# TA_v2_Deck.net
KiCad netlist of a schematic drawn in EAGLE
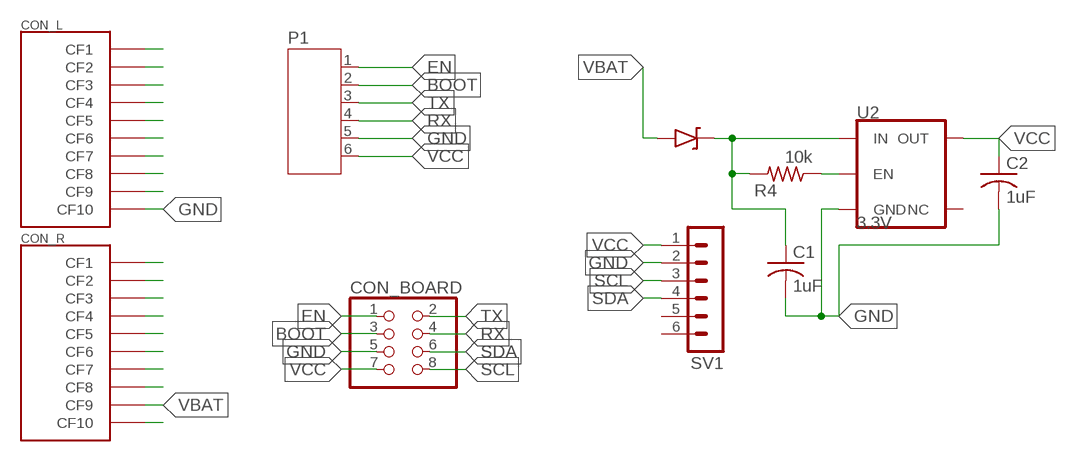
[diagram p0: schematic, sheet 1]

(export (version "E")
  (design (tool "Eeschema 10.0.6"))
  (components
    (comp (ref "C1")
      (value "1uF")
      (footprint "eagle-import:C0805")
      (libsource (lib "eagle-import") (part "C-USC0805"))
    )
    (comp (ref "C2")
      (value "1uF")
      (footprint "eagle-import:C0805")
      (libsource (lib "eagle-import") (part "C-USC0805"))
    )
    (comp (ref "CON_BOARD")
      (value "PINHD-2X4")
      (footprint "eagle-import:2X04")
      (libsource (lib "eagle-import") (part "PINHD-2X4"))
    )
    (comp (ref "CON_L")
      (value "FEMALE_CON")
      (footprint "eagle-import:FEMALE_HEADER_2")
      (libsource (lib "eagle-import") (part "FEMALE_CON"))
    )
    (comp (ref "CON_R")
      (value "FEMALE_CON")
      (footprint "eagle-import:FEMALE_HEADER_2")
      (libsource (lib "eagle-import") (part "FEMALE_CON"))
    )
    (comp (ref "P1")
      (value "JST-PH6")
      (footprint "eagle-import:JST-PH6")
      (libsource (lib "eagle-import") (part "JST-PH6"))
    )
    (comp (ref "R4")
      (value "10k")
      (footprint "eagle-import:R0603")
      (libsource (lib "eagle-import") (part "R-US_R0603"))
    )
    (comp (ref "SV1")
      (value "MA06-1")
      (footprint "eagle-import:MA06-1")
      (libsource (lib "eagle-import") (part "MA06-1"))
    )
    (comp (ref "U$2")
      (value "1N5819")
      (footprint "eagle-import:SOT-323")
      (libsource (lib "eagle-import") (part "1N5819"))
    )
    (comp (ref "U2")
      (value "3.3V")
      (footprint "eagle-import:SOT23-5")
      (libsource (lib "eagle-import") (part "V_REG_AP2112K-3.3V"))
    )
  )
  (nets
    (net (code "1") (name "BOOT") (class "Default")
      (node (ref "CON_BOARD") (pin "3") (pinfunction "3_3") (pintype "passive"))
      (node (ref "P1") (pin "2") (pinfunction "2_2") (pintype "passive"))
    )
    (net (code "2") (name "EN") (class "Default")
      (node (ref "CON_BOARD") (pin "1") (pinfunction "1_1") (pintype "passive"))
      (node (ref "P1") (pin "1") (pinfunction "1_1") (pintype "passive"))
    )
    (net (code "3") (name "GND") (class "Default")
      (node (ref "C1") (pin "2") (pinfunction "2_2") (pintype "passive"))
      (node (ref "C2") (pin "2") (pinfunction "2_2") (pintype "passive"))
      (node (ref "CON_BOARD") (pin "5") (pinfunction "5_5") (pintype "passive"))
      (node (ref "CON_L") (pin "CF10") (pinfunction "CF10_CF10") (pintype "bidirectional"))
      (node (ref "P1") (pin "5") (pinfunction "5_5") (pintype "passive"))
      (node (ref "SV1") (pin "2") (pinfunction "2_2") (pintype "passive"))
      (node (ref "U2") (pin "2") (pinfunction "GND_2") (pintype "input"))
    )
    (net (code "4") (name "Net-(U2-EN)") (class "Default")
      (node (ref "R4") (pin "1") (pinfunction "1_1") (pintype "passive"))
      (node (ref "U2") (pin "3") (pinfunction "EN_3") (pintype "input"))
    )
    (net (code "5") (name "Net-(U2-IN)") (class "Default")
      (node (ref "C1") (pin "1") (pinfunction "1_1") (pintype "passive"))
      (node (ref "R4") (pin "2") (pinfunction "2_2") (pintype "passive"))
      (node (ref "U$2") (pin "K") (pinfunction "K_K") (pintype "bidirectional"))
      (node (ref "U2") (pin "1") (pinfunction "IN_1") (pintype "input"))
    )
    (net (code "6") (name "RX") (class "Default")
      (node (ref "CON_BOARD") (pin "4") (pinfunction "4_4") (pintype "passive"))
      (node (ref "P1") (pin "4") (pinfunction "4_4") (pintype "passive"))
    )
    (net (code "7") (name "SCL") (class "Default")
      (node (ref "CON_BOARD") (pin "8") (pinfunction "8_8") (pintype "passive"))
      (node (ref "SV1") (pin "3") (pinfunction "3_3") (pintype "passive"))
    )
    (net (code "8") (name "SDA") (class "Default")
      (node (ref "CON_BOARD") (pin "6") (pinfunction "6_6") (pintype "passive"))
      (node (ref "SV1") (pin "4") (pinfunction "4_4") (pintype "passive"))
    )
    (net (code "9") (name "TX") (class "Default")
      (node (ref "CON_BOARD") (pin "2") (pinfunction "2_2") (pintype "passive"))
      (node (ref "P1") (pin "3") (pinfunction "3_3") (pintype "passive"))
    )
    (net (code "10") (name "VBAT") (class "Default")
      (node (ref "CON_R") (pin "CF9") (pinfunction "CF9_CF9") (pintype "bidirectional"))
      (node (ref "U$2") (pin "A") (pinfunction "A_A") (pintype "bidirectional"))
    )
    (net (code "11") (name "VCC") (class "Default")
      (node (ref "C2") (pin "1") (pinfunction "1_1") (pintype "passive"))
      (node (ref "CON_BOARD") (pin "7") (pinfunction "7_7") (pintype "passive"))
      (node (ref "P1") (pin "6") (pinfunction "6_6") (pintype "passive"))
      (node (ref "SV1") (pin "1") (pinfunction "1_1") (pintype "passive"))
      (node (ref "U2") (pin "5") (pinfunction "OUT_5") (pintype "passive"))
    )
    (net (code "12") (name "unconnected-(CON_L-PadCF1)") (class "Default")
      (node (ref "CON_L") (pin "CF1") (pinfunction "CF1_CF1") (pintype "bidirectional"))
    )
    (net (code "13") (name "unconnected-(CON_L-PadCF2)") (class "Default")
      (node (ref "CON_L") (pin "CF2") (pinfunction "CF2_CF2") (pintype "bidirectional"))
    )
    (net (code "14") (name "unconnected-(CON_L-PadCF3)") (class "Default")
      (node (ref "CON_L") (pin "CF3") (pinfunction "CF3_CF3") (pintype "bidirectional"))
    )
    (net (code "15") (name "unconnected-(CON_L-PadCF4)") (class "Default")
      (node (ref "CON_L") (pin "CF4") (pinfunction "CF4_CF4") (pintype "bidirectional"))
    )
    (net (code "16") (name "unconnected-(CON_L-PadCF5)") (class "Default")
      (node (ref "CON_L") (pin "CF5") (pinfunction "CF5_CF5") (pintype "bidirectional"))
    )
    (net (code "17") (name "unconnected-(CON_L-PadCF6)") (class "Default")
      (node (ref "CON_L") (pin "CF6") (pinfunction "CF6_CF6") (pintype "bidirectional"))
    )
    (net (code "18") (name "unconnected-(CON_L-PadCF7)") (class "Default")
      (node (ref "CON_L") (pin "CF7") (pinfunction "CF7_CF7") (pintype "bidirectional"))
    )
    (net (code "19") (name "unconnected-(CON_L-PadCF8)") (class "Default")
      (node (ref "CON_L") (pin "CF8") (pinfunction "CF8_CF8") (pintype "bidirectional"))
    )
    (net (code "20") (name "unconnected-(CON_L-PadCF9)") (class "Default")
      (node (ref "CON_L") (pin "CF9") (pinfunction "CF9_CF9") (pintype "bidirectional"))
    )
    (net (code "21") (name "unconnected-(CON_R-PadCF1)") (class "Default")
      (node (ref "CON_R") (pin "CF1") (pinfunction "CF1_CF1") (pintype "bidirectional"))
    )
    (net (code "22") (name "unconnected-(CON_R-PadCF2)") (class "Default")
      (node (ref "CON_R") (pin "CF2") (pinfunction "CF2_CF2") (pintype "bidirectional"))
    )
    (net (code "23") (name "unconnected-(CON_R-PadCF3)") (class "Default")
      (node (ref "CON_R") (pin "CF3") (pinfunction "CF3_CF3") (pintype "bidirectional"))
    )
    (net (code "24") (name "unconnected-(CON_R-PadCF4)") (class "Default")
      (node (ref "CON_R") (pin "CF4") (pinfunction "CF4_CF4") (pintype "bidirectional"))
    )
    (net (code "25") (name "unconnected-(CON_R-PadCF5)") (class "Default")
      (node (ref "CON_R") (pin "CF5") (pinfunction "CF5_CF5") (pintype "bidirectional"))
    )
    (net (code "26") (name "unconnected-(CON_R-PadCF6)") (class "Default")
      (node (ref "CON_R") (pin "CF6") (pinfunction "CF6_CF6") (pintype "bidirectional"))
    )
    (net (code "27") (name "unconnected-(CON_R-PadCF7)") (class "Default")
      (node (ref "CON_R") (pin "CF7") (pinfunction "CF7_CF7") (pintype "bidirectional"))
    )
    (net (code "28") (name "unconnected-(CON_R-PadCF8)") (class "Default")
      (node (ref "CON_R") (pin "CF8") (pinfunction "CF8_CF8") (pintype "bidirectional"))
    )
    (net (code "29") (name "unconnected-(CON_R-PadCF10)") (class "Default")
      (node (ref "CON_R") (pin "CF10") (pinfunction "CF10_CF10") (pintype "bidirectional"))
    )
    (net (code "30") (name "unconnected-(SV1-Pad5)") (class "Default")
      (node (ref "SV1") (pin "5") (pinfunction "5_5") (pintype "passive"))
    )
    (net (code "31") (name "unconnected-(SV1-Pad6)") (class "Default")
      (node (ref "SV1") (pin "6") (pinfunction "6_6") (pintype "passive"))
    )
    (net (code "32") (name "unconnected-(U2-NC-Pad4)") (class "Default")
      (node (ref "U2") (pin "4") (pinfunction "NC_4") (pintype "no_connect"))
    )
  )
)
